# Microcontroller.net
KiCad netlist of a schematic drawn in Altium Designer
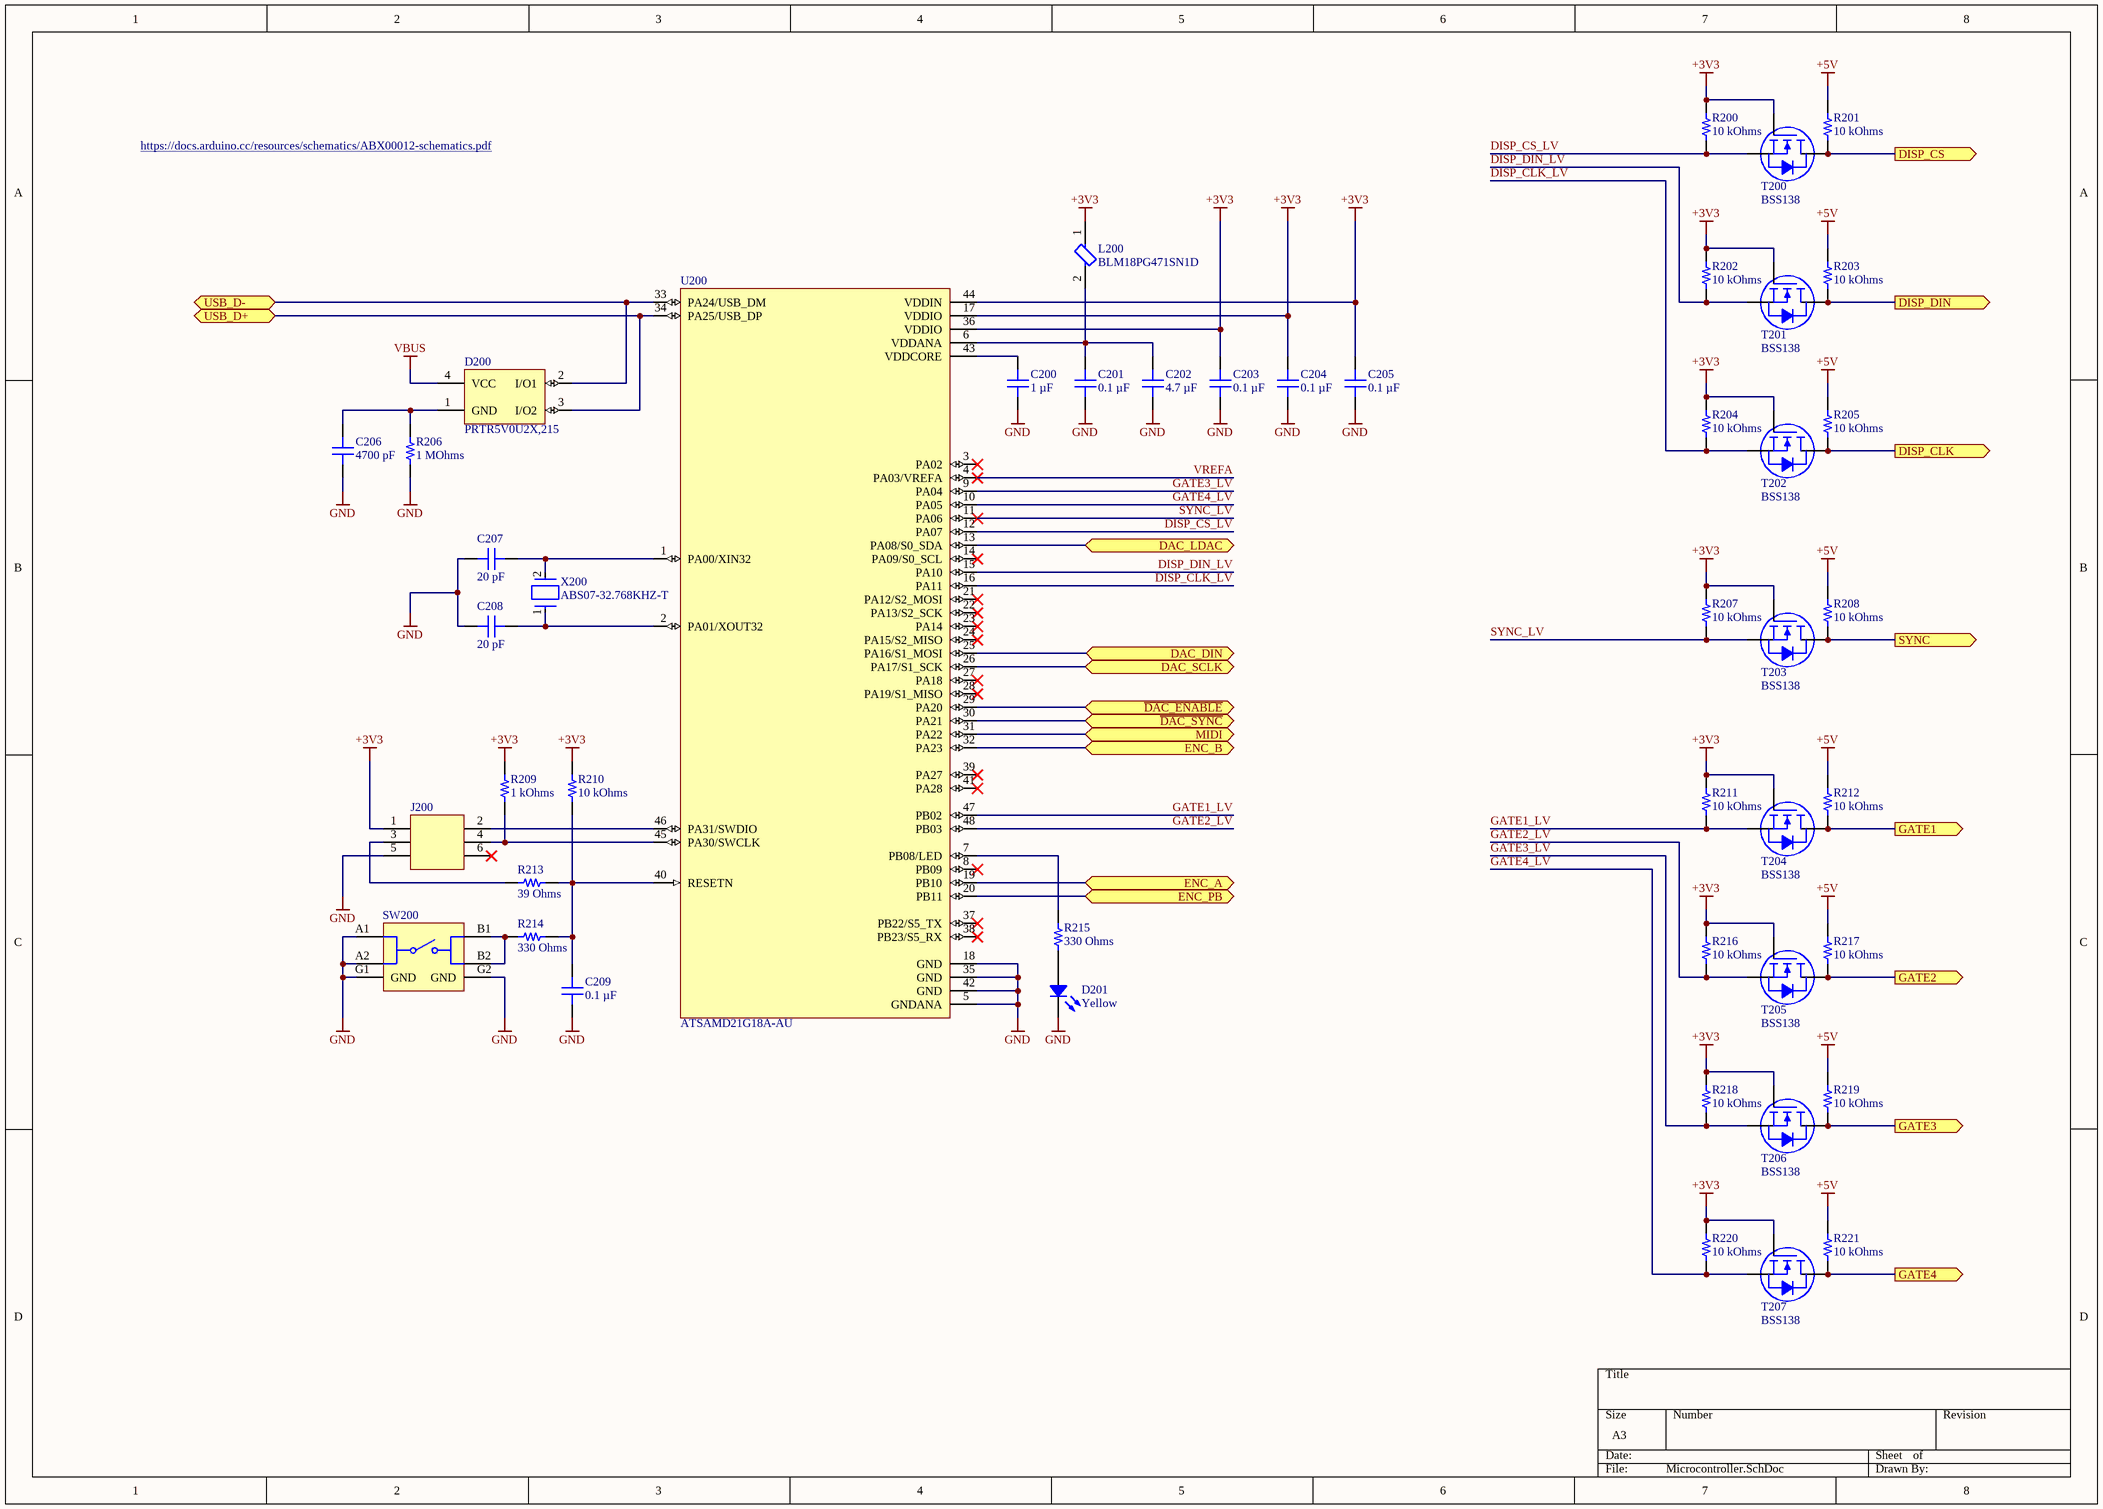
[diagram p0: Microcontroller.SchDoc]

(export (version "E")
  (design (tool "Eeschema 10.0.6"))
  (components
    (comp (ref "C200")
      (value "1 µF")
      (footprint "CAP 0603_1608")
      (description "CAP CER 1UF 10V X7R 0603")
      (fields (field (name "PART NUMBER") "CC0603KRX7R6BB105") (field (name "MANUFACTURER") "Yageo"))
      (libsource (lib "Celestial Altium Library") (part "Capacitor"))
    )
    (comp (ref "C201")
      (value "0.1 µF")
      (footprint "CAP 0603_1608")
      (description "CAP CER 0.1UF 16V X7R 0603")
      (fields (field (name "PART NUMBER") "CS0603KRX7R7BB104") (field (name "MANUFACTURER") "Yageo"))
      (libsource (lib "Celestial Altium Library") (part "Capacitor"))
    )
    (comp (ref "C202")
      (value "4.7 µF")
      (footprint "CAP 0603_1608")
      (description "CAP CER 4.7UF 10V X5R 0603")
      (fields (field (name "PART NUMBER") "CC0603MRX5R6BB475") (field (name "MANUFACTURER") "Yageo"))
      (libsource (lib "Celestial Altium Library") (part "Capacitor"))
    )
    (comp (ref "C203")
      (value "0.1 µF")
      (footprint "CAP 0603_1608")
      (description "CAP CER 0.1UF 16V X7R 0603")
      (fields (field (name "PART NUMBER") "CS0603KRX7R7BB104") (field (name "MANUFACTURER") "Yageo"))
      (libsource (lib "Celestial Altium Library") (part "Capacitor"))
    )
    (comp (ref "C204")
      (value "0.1 µF")
      (footprint "CAP 0603_1608")
      (description "CAP CER 0.1UF 16V X7R 0603")
      (fields (field (name "PART NUMBER") "CS0603KRX7R7BB104") (field (name "MANUFACTURER") "Yageo"))
      (libsource (lib "Celestial Altium Library") (part "Capacitor"))
    )
    (comp (ref "C205")
      (value "0.1 µF")
      (footprint "CAP 0603_1608")
      (description "CAP CER 0.1UF 16V X7R 0603")
      (fields (field (name "PART NUMBER") "CS0603KRX7R7BB104") (field (name "MANUFACTURER") "Yageo"))
      (libsource (lib "Celestial Altium Library") (part "Capacitor"))
    )
    (comp (ref "C206")
      (value "4700 pF")
      (footprint "CAP 0603_1608")
      (description "CAP CER 4700PF 50V X7R 0603")
      (fields (field (name "PART NUMBER") "CC0603JRX7R9BB472") (field (name "MANUFACTURER") "Yageo"))
      (libsource (lib "Celestial Altium Library") (part "Capacitor"))
    )
    (comp (ref "C207")
      (value "20 pF")
      (footprint "CAP 0603_1608")
      (description "CAP CER 20PF 50V C0G/NPO 0603")
      (fields (field (name "PART NUMBER") "CC0603JRNPO9BN200") (field (name "MANUFACTURER") "Yageo"))
      (libsource (lib "Celestial Altium Library") (part "Capacitor"))
    )
    (comp (ref "C208")
      (value "20 pF")
      (footprint "CAP 0603_1608")
      (description "CAP CER 20PF 50V C0G/NPO 0603")
      (fields (field (name "PART NUMBER") "CC0603JRNPO9BN200") (field (name "MANUFACTURER") "Yageo"))
      (libsource (lib "Celestial Altium Library") (part "Capacitor"))
    )
    (comp (ref "C209")
      (value "0.1 µF")
      (footprint "CAP 0603_1608")
      (description "CAP CER 0.1UF 16V X7R 0603")
      (fields (field (name "PART NUMBER") "CS0603KRX7R7BB104") (field (name "MANUFACTURER") "Yageo"))
      (libsource (lib "Celestial Altium Library") (part "Capacitor"))
    )
    (comp (ref "D200")
      (value "PRTR5V0U2X,215")
      (footprint "NXP-SOT143B-4_V")
      (fields (field (name "MANUFACTURER") "NXP Semiconductors"))
      (libsource (lib "LabratsSynthLib") (part "PRTR5V0U2X,215"))
    )
    (comp (ref "D201")
      (value "Yellow")
      (footprint "LED 0603_1608 YELLOW")
      (description "LED YELLOW 0603 SMD")
      (fields (field (name "PART NUMBER") "5990040007F") (field (name "MANUFACTURER") "Dialight"))
      (libsource (lib "Celestial Altium Library") (part "LED"))
    )
    (comp (ref "J200")
      (value "61030621121")
      (footprint "61030621121")
      (libsource (lib "LabratsSynthLib") (part "61030621121"))
    )
    (comp (ref "L200")
      (value "BLM18PG471SN1D")
      (footprint "FP-BLM18-0_15-t0_8-MFG")
      (description "Chip Ferrite Bead, 0603, 470Ω @ 100MHz, 0.2Ω, 25%, 1A")
      (fields (field (name "TOLERANCE") "25%"))
      (libsource (lib "Altium Content Vault") (part "5f30dd21d616792df468990f7003faa"))
    )
    (comp (ref "R200")
      (value "10 kOhms")
      (footprint "RES 0603_1608")
      (description "RES SMD 10K OHM 1% 1/10W 0603")
      (fields (field (name "PART NUMBER") "CRCW060310K0FKTA") (field (name "MANUFACTURER") "Vishay Dale"))
      (libsource (lib "Celestial Altium Library") (part "Resistor"))
    )
    (comp (ref "R201")
      (value "10 kOhms")
      (footprint "RES 0603_1608")
      (description "RES SMD 10K OHM 1% 1/10W 0603")
      (fields (field (name "PART NUMBER") "CRCW060310K0FKTA") (field (name "MANUFACTURER") "Vishay Dale"))
      (libsource (lib "Celestial Altium Library") (part "Resistor"))
    )
    (comp (ref "R202")
      (value "10 kOhms")
      (footprint "RES 0603_1608")
      (description "RES SMD 10K OHM 1% 1/10W 0603")
      (fields (field (name "PART NUMBER") "CRCW060310K0FKTA") (field (name "MANUFACTURER") "Vishay Dale"))
      (libsource (lib "Celestial Altium Library") (part "Resistor"))
    )
    (comp (ref "R203")
      (value "10 kOhms")
      (footprint "RES 0603_1608")
      (description "RES SMD 10K OHM 1% 1/10W 0603")
      (fields (field (name "PART NUMBER") "CRCW060310K0FKTA") (field (name "MANUFACTURER") "Vishay Dale"))
      (libsource (lib "Celestial Altium Library") (part "Resistor"))
    )
    (comp (ref "R204")
      (value "10 kOhms")
      (footprint "RES 0603_1608")
      (description "RES SMD 10K OHM 1% 1/10W 0603")
      (fields (field (name "PART NUMBER") "CRCW060310K0FKTA") (field (name "MANUFACTURER") "Vishay Dale"))
      (libsource (lib "Celestial Altium Library") (part "Resistor"))
    )
    (comp (ref "R205")
      (value "10 kOhms")
      (footprint "RES 0603_1608")
      (description "RES SMD 10K OHM 1% 1/10W 0603")
      (fields (field (name "PART NUMBER") "CRCW060310K0FKTA") (field (name "MANUFACTURER") "Vishay Dale"))
      (libsource (lib "Celestial Altium Library") (part "Resistor"))
    )
    (comp (ref "R206")
      (value "1 MOhms")
      (footprint "RES 0603_1608")
      (description "RES SMD 1M OHM 1% 1/10W 0603")
      (fields (field (name "PART NUMBER") "CRCW06031M00FKEA") (field (name "MANUFACTURER") "Vishay Dale"))
      (libsource (lib "Celestial Altium Library") (part "Resistor"))
    )
    (comp (ref "R207")
      (value "10 kOhms")
      (footprint "RES 0603_1608")
      (description "RES SMD 10K OHM 1% 1/10W 0603")
      (fields (field (name "PART NUMBER") "CRCW060310K0FKTA") (field (name "MANUFACTURER") "Vishay Dale"))
      (libsource (lib "Celestial Altium Library") (part "Resistor"))
    )
    (comp (ref "R208")
      (value "10 kOhms")
      (footprint "RES 0603_1608")
      (description "RES SMD 10K OHM 1% 1/10W 0603")
      (fields (field (name "PART NUMBER") "CRCW060310K0FKTA") (field (name "MANUFACTURER") "Vishay Dale"))
      (libsource (lib "Celestial Altium Library") (part "Resistor"))
    )
    (comp (ref "R209")
      (value "1 kOhms")
      (footprint "RES 0603_1608")
      (description "RES SMD 1K OHM 1% 1/10W 0603")
      (fields (field (name "PART NUMBER") "CRCW06031K00FKEB") (field (name "MANUFACTURER") "Vishay Dale"))
      (libsource (lib "Celestial Altium Library") (part "Resistor"))
    )
    (comp (ref "R210")
      (value "10 kOhms")
      (footprint "RES 0603_1608")
      (description "RES SMD 10K OHM 1% 1/10W 0603")
      (fields (field (name "PART NUMBER") "CRCW060310K0FKTA") (field (name "MANUFACTURER") "Vishay Dale"))
      (libsource (lib "Celestial Altium Library") (part "Resistor"))
    )
    (comp (ref "R211")
      (value "10 kOhms")
      (footprint "RES 0603_1608")
      (description "RES SMD 10K OHM 1% 1/10W 0603")
      (fields (field (name "PART NUMBER") "CRCW060310K0FKTA") (field (name "MANUFACTURER") "Vishay Dale"))
      (libsource (lib "Celestial Altium Library") (part "Resistor"))
    )
    (comp (ref "R212")
      (value "10 kOhms")
      (footprint "RES 0603_1608")
      (description "RES SMD 10K OHM 1% 1/10W 0603")
      (fields (field (name "PART NUMBER") "CRCW060310K0FKTA") (field (name "MANUFACTURER") "Vishay Dale"))
      (libsource (lib "Celestial Altium Library") (part "Resistor"))
    )
    (comp (ref "R213")
      (value "39 Ohms")
      (footprint "RES 0603_1608")
      (description "RES SMD 39 OHM 1% 1/10W 0603")
      (fields (field (name "PART NUMBER") "CRCW060339R0FKEA") (field (name "MANUFACTURER") "Vishay Dale"))
      (libsource (lib "Celestial Altium Library") (part "Resistor"))
    )
    (comp (ref "R214")
      (value "330 Ohms")
      (footprint "RES 0603_1608")
      (description "RES 330 OHM 1% 1/10W 0603")
      (fields (field (name "PART NUMBER") "CRCW0603330RFKEAC") (field (name "MANUFACTURER") "Vishay Dale"))
      (libsource (lib "Celestial Altium Library") (part "Resistor"))
    )
    (comp (ref "R215")
      (value "330 Ohms")
      (footprint "RES 0603_1608")
      (description "RES 330 OHM 1% 1/10W 0603")
      (fields (field (name "PART NUMBER") "CRCW0603330RFKEAC") (field (name "MANUFACTURER") "Vishay Dale"))
      (libsource (lib "Celestial Altium Library") (part "Resistor"))
    )
    (comp (ref "R216")
      (value "10 kOhms")
      (footprint "RES 0603_1608")
      (description "RES SMD 10K OHM 1% 1/10W 0603")
      (fields (field (name "PART NUMBER") "CRCW060310K0FKTA") (field (name "MANUFACTURER") "Vishay Dale"))
      (libsource (lib "Celestial Altium Library") (part "Resistor"))
    )
    (comp (ref "R217")
      (value "10 kOhms")
      (footprint "RES 0603_1608")
      (description "RES SMD 10K OHM 1% 1/10W 0603")
      (fields (field (name "PART NUMBER") "CRCW060310K0FKTA") (field (name "MANUFACTURER") "Vishay Dale"))
      (libsource (lib "Celestial Altium Library") (part "Resistor"))
    )
    (comp (ref "R218")
      (value "10 kOhms")
      (footprint "RES 0603_1608")
      (description "RES SMD 10K OHM 1% 1/10W 0603")
      (fields (field (name "PART NUMBER") "CRCW060310K0FKTA") (field (name "MANUFACTURER") "Vishay Dale"))
      (libsource (lib "Celestial Altium Library") (part "Resistor"))
    )
    (comp (ref "R219")
      (value "10 kOhms")
      (footprint "RES 0603_1608")
      (description "RES SMD 10K OHM 1% 1/10W 0603")
      (fields (field (name "PART NUMBER") "CRCW060310K0FKTA") (field (name "MANUFACTURER") "Vishay Dale"))
      (libsource (lib "Celestial Altium Library") (part "Resistor"))
    )
    (comp (ref "R220")
      (value "10 kOhms")
      (footprint "RES 0603_1608")
      (description "RES SMD 10K OHM 1% 1/10W 0603")
      (fields (field (name "PART NUMBER") "CRCW060310K0FKTA") (field (name "MANUFACTURER") "Vishay Dale"))
      (libsource (lib "Celestial Altium Library") (part "Resistor"))
    )
    (comp (ref "R221")
      (value "10 kOhms")
      (footprint "RES 0603_1608")
      (description "RES SMD 10K OHM 1% 1/10W 0603")
      (fields (field (name "PART NUMBER") "CRCW060310K0FKTA") (field (name "MANUFACTURER") "Vishay Dale"))
      (libsource (lib "Celestial Altium Library") (part "Resistor"))
    )
    (comp (ref "SW200")
      (value "435171014816")
      (footprint "435171014816")
      (description "Tactile Switch, Spst-no, 0.05A, 12V, SMD;")
      (libsource (lib "Altium Content Vault") (part "SPST-NO_4P_2GND"))
    )
    (comp (ref "T200")
      (value "BSS138")
      (footprint "ON SEMI SOT-23-3")
      (description "MOSFET N-CH 50V 220MA SOT-23")
      (fields (field (name "MANUFACTURER") "ON Semiconductor"))
      (libsource (lib "Celestial Altium Library") (part "ON SEMI MOSFET N-CH SOT-23-3"))
    )
    (comp (ref "T201")
      (value "BSS138")
      (footprint "ON SEMI SOT-23-3")
      (description "MOSFET N-CH 50V 220MA SOT-23")
      (fields (field (name "MANUFACTURER") "ON Semiconductor"))
      (libsource (lib "Celestial Altium Library") (part "ON SEMI MOSFET N-CH SOT-23-3"))
    )
    (comp (ref "T202")
      (value "BSS138")
      (footprint "ON SEMI SOT-23-3")
      (description "MOSFET N-CH 50V 220MA SOT-23")
      (fields (field (name "MANUFACTURER") "ON Semiconductor"))
      (libsource (lib "Celestial Altium Library") (part "ON SEMI MOSFET N-CH SOT-23-3"))
    )
    (comp (ref "T203")
      (value "BSS138")
      (footprint "ON SEMI SOT-23-3")
      (description "MOSFET N-CH 50V 220MA SOT-23")
      (fields (field (name "MANUFACTURER") "ON Semiconductor"))
      (libsource (lib "Celestial Altium Library") (part "ON SEMI MOSFET N-CH SOT-23-3"))
    )
    (comp (ref "T204")
      (value "BSS138")
      (footprint "ON SEMI SOT-23-3")
      (description "MOSFET N-CH 50V 220MA SOT-23")
      (fields (field (name "MANUFACTURER") "ON Semiconductor"))
      (libsource (lib "Celestial Altium Library") (part "ON SEMI MOSFET N-CH SOT-23-3"))
    )
    (comp (ref "T205")
      (value "BSS138")
      (footprint "ON SEMI SOT-23-3")
      (description "MOSFET N-CH 50V 220MA SOT-23")
      (fields (field (name "MANUFACTURER") "ON Semiconductor"))
      (libsource (lib "Celestial Altium Library") (part "ON SEMI MOSFET N-CH SOT-23-3"))
    )
    (comp (ref "T206")
      (value "BSS138")
      (footprint "ON SEMI SOT-23-3")
      (description "MOSFET N-CH 50V 220MA SOT-23")
      (fields (field (name "MANUFACTURER") "ON Semiconductor"))
      (libsource (lib "Celestial Altium Library") (part "ON SEMI MOSFET N-CH SOT-23-3"))
    )
    (comp (ref "T207")
      (value "BSS138")
      (footprint "ON SEMI SOT-23-3")
      (description "MOSFET N-CH 50V 220MA SOT-23")
      (fields (field (name "MANUFACTURER") "ON Semiconductor"))
      (libsource (lib "Celestial Altium Library") (part "ON SEMI MOSFET N-CH SOT-23-3"))
    )
    (comp (ref "U200")
      (value "ATSAMD21G18A-AU")
      (footprint "ATML-TQFP48")
      (fields (field (name "MANUFACTURER") "Atmel"))
      (libsource (lib "LabratsSynthLib") (part "ATSAMD21G18A-AU"))
    )
    (comp (ref "X200")
      (value "ABS07-32.768KHZ-T")
      (footprint "FP-ABS07-MFG")
      (description "Crystal 32.768kHz ±20ppm (Tol) 12.5pF FUND 70kΩ 2-Pin CSMD T/R")
      (fields (field (name "TOLERANCE") "20ppm"))
      (libsource (lib "Altium Content Vault") (part "c23a69dc6c9e2f18f2079038eb95dd1"))
    )
  )
  (nets
    (net (code "1") (name "+3V3") (class "Default")
      (node (ref "C203") (pin "2") (pinfunction "2_2") (pintype "passive"))
      (node (ref "C204") (pin "2") (pinfunction "2_2") (pintype "passive"))
      (node (ref "C205") (pin "2") (pinfunction "2_2") (pintype "passive"))
      (node (ref "J200") (pin "1") (pinfunction "1_1") (pintype "passive"))
      (node (ref "L200") (pin "1") (pinfunction "1_1") (pintype "passive"))
      (node (ref "R200") (pin "2") (pinfunction "2_2") (pintype "passive"))
      (node (ref "R202") (pin "2") (pinfunction "2_2") (pintype "passive"))
      (node (ref "R204") (pin "2") (pinfunction "2_2") (pintype "passive"))
      (node (ref "R207") (pin "2") (pinfunction "2_2") (pintype "passive"))
      (node (ref "R209") (pin "2") (pinfunction "2_2") (pintype "passive"))
      (node (ref "R210") (pin "2") (pinfunction "2_2") (pintype "passive"))
      (node (ref "R211") (pin "2") (pinfunction "2_2") (pintype "passive"))
      (node (ref "R216") (pin "2") (pinfunction "2_2") (pintype "passive"))
      (node (ref "R218") (pin "2") (pinfunction "2_2") (pintype "passive"))
      (node (ref "R220") (pin "2") (pinfunction "2_2") (pintype "passive"))
      (node (ref "T200") (pin "1") (pinfunction "G_1") (pintype "passive"))
      (node (ref "T201") (pin "1") (pinfunction "G_1") (pintype "passive"))
      (node (ref "T202") (pin "1") (pinfunction "G_1") (pintype "passive"))
      (node (ref "T203") (pin "1") (pinfunction "G_1") (pintype "passive"))
      (node (ref "T204") (pin "1") (pinfunction "G_1") (pintype "passive"))
      (node (ref "T205") (pin "1") (pinfunction "G_1") (pintype "passive"))
      (node (ref "T206") (pin "1") (pinfunction "G_1") (pintype "passive"))
      (node (ref "T207") (pin "1") (pinfunction "G_1") (pintype "passive"))
      (node (ref "U200") (pin "17") (pinfunction "VDDIO_17") (pintype "power_in"))
      (node (ref "U200") (pin "36") (pinfunction "VDDIO_36") (pintype "power_in"))
      (node (ref "U200") (pin "44") (pinfunction "VDDIN_44") (pintype "power_in"))
    )
    (net (code "2") (name "+5V") (class "Default")
      (node (ref "R201") (pin "2") (pinfunction "2_2") (pintype "passive"))
      (node (ref "R203") (pin "2") (pinfunction "2_2") (pintype "passive"))
      (node (ref "R205") (pin "2") (pinfunction "2_2") (pintype "passive"))
      (node (ref "R208") (pin "2") (pinfunction "2_2") (pintype "passive"))
      (node (ref "R212") (pin "2") (pinfunction "2_2") (pintype "passive"))
      (node (ref "R217") (pin "2") (pinfunction "2_2") (pintype "passive"))
      (node (ref "R219") (pin "2") (pinfunction "2_2") (pintype "passive"))
      (node (ref "R221") (pin "2") (pinfunction "2_2") (pintype "passive"))
    )
    (net (code "3") (name "/DAC_DIN") (class "Default")
      (node (ref "U200") (pin "25") (pinfunction "PA16/S1_MOSI_25") (pintype "bidirectional"))
    )
    (net (code "4") (name "/DAC_LDAC") (class "Default")
      (node (ref "U200") (pin "13") (pinfunction "PA08/S0_SDA_13") (pintype "bidirectional"))
    )
    (net (code "5") (name "/DAC_SCLK") (class "Default")
      (node (ref "U200") (pin "26") (pinfunction "PA17/S1_SCK_26") (pintype "bidirectional"))
    )
    (net (code "6") (name "/DISP_CLK") (class "Default")
      (node (ref "R205") (pin "1") (pinfunction "1_1") (pintype "passive"))
      (node (ref "T202") (pin "3") (pinfunction "D_3") (pintype "passive"))
    )
    (net (code "7") (name "/DISP_CLK_LV") (class "Default")
      (node (ref "R204") (pin "1") (pinfunction "1_1") (pintype "passive"))
      (node (ref "T202") (pin "2") (pinfunction "S_2") (pintype "passive"))
      (node (ref "U200") (pin "16") (pinfunction "PA11_16") (pintype "bidirectional"))
    )
    (net (code "8") (name "/DISP_CS") (class "Default")
      (node (ref "R201") (pin "1") (pinfunction "1_1") (pintype "passive"))
      (node (ref "T200") (pin "3") (pinfunction "D_3") (pintype "passive"))
    )
    (net (code "9") (name "/DISP_CS_LV") (class "Default")
      (node (ref "R200") (pin "1") (pinfunction "1_1") (pintype "passive"))
      (node (ref "T200") (pin "2") (pinfunction "S_2") (pintype "passive"))
      (node (ref "U200") (pin "12") (pinfunction "PA07_12") (pintype "bidirectional"))
    )
    (net (code "10") (name "/DISP_DIN") (class "Default")
      (node (ref "R203") (pin "1") (pinfunction "1_1") (pintype "passive"))
      (node (ref "T201") (pin "3") (pinfunction "D_3") (pintype "passive"))
    )
    (net (code "11") (name "/DISP_DIN_LV") (class "Default")
      (node (ref "R202") (pin "1") (pinfunction "1_1") (pintype "passive"))
      (node (ref "T201") (pin "2") (pinfunction "S_2") (pintype "passive"))
      (node (ref "U200") (pin "15") (pinfunction "PA10_15") (pintype "bidirectional"))
    )
    (net (code "12") (name "/ENC_A") (class "Default")
      (node (ref "U200") (pin "19") (pinfunction "PB10_19") (pintype "bidirectional"))
    )
    (net (code "13") (name "/ENC_B") (class "Default")
      (node (ref "U200") (pin "32") (pinfunction "PA23_32") (pintype "bidirectional"))
    )
    (net (code "14") (name "/ENC_PB") (class "Default")
      (node (ref "U200") (pin "20") (pinfunction "PB11_20") (pintype "bidirectional"))
    )
    (net (code "15") (name "/GATE1") (class "Default")
      (node (ref "R212") (pin "1") (pinfunction "1_1") (pintype "passive"))
      (node (ref "T204") (pin "3") (pinfunction "D_3") (pintype "passive"))
    )
    (net (code "16") (name "/GATE1_LV") (class "Default")
      (node (ref "R211") (pin "1") (pinfunction "1_1") (pintype "passive"))
      (node (ref "T204") (pin "2") (pinfunction "S_2") (pintype "passive"))
      (node (ref "U200") (pin "47") (pinfunction "PB02_47") (pintype "bidirectional"))
    )
    (net (code "17") (name "/GATE2") (class "Default")
      (node (ref "R217") (pin "1") (pinfunction "1_1") (pintype "passive"))
      (node (ref "T205") (pin "3") (pinfunction "D_3") (pintype "passive"))
    )
    (net (code "18") (name "/GATE2_LV") (class "Default")
      (node (ref "R216") (pin "1") (pinfunction "1_1") (pintype "passive"))
      (node (ref "T205") (pin "2") (pinfunction "S_2") (pintype "passive"))
      (node (ref "U200") (pin "48") (pinfunction "PB03_48") (pintype "bidirectional"))
    )
    (net (code "19") (name "/GATE3") (class "Default")
      (node (ref "R219") (pin "1") (pinfunction "1_1") (pintype "passive"))
      (node (ref "T206") (pin "3") (pinfunction "D_3") (pintype "passive"))
    )
    (net (code "20") (name "/GATE3_LV") (class "Default")
      (node (ref "R218") (pin "1") (pinfunction "1_1") (pintype "passive"))
      (node (ref "T206") (pin "2") (pinfunction "S_2") (pintype "passive"))
      (node (ref "U200") (pin "9") (pinfunction "PA04_9") (pintype "bidirectional"))
    )
    (net (code "21") (name "/GATE4") (class "Default")
      (node (ref "R221") (pin "1") (pinfunction "1_1") (pintype "passive"))
      (node (ref "T207") (pin "3") (pinfunction "D_3") (pintype "passive"))
    )
    (net (code "22") (name "/GATE4_LV") (class "Default")
      (node (ref "R220") (pin "1") (pinfunction "1_1") (pintype "passive"))
      (node (ref "T207") (pin "2") (pinfunction "S_2") (pintype "passive"))
      (node (ref "U200") (pin "10") (pinfunction "PA05_10") (pintype "bidirectional"))
    )
    (net (code "23") (name "/MIDI") (class "Default")
      (node (ref "U200") (pin "31") (pinfunction "PA22_31") (pintype "bidirectional"))
    )
    (net (code "24") (name "/SYNC") (class "Default")
      (node (ref "R208") (pin "1") (pinfunction "1_1") (pintype "passive"))
      (node (ref "T203") (pin "3") (pinfunction "D_3") (pintype "passive"))
    )
    (net (code "25") (name "/SYNC_LV") (class "Default")
      (node (ref "R207") (pin "1") (pinfunction "1_1") (pintype "passive"))
      (node (ref "T203") (pin "2") (pinfunction "S_2") (pintype "passive"))
      (node (ref "U200") (pin "11") (pinfunction "PA06_11") (pintype "bidirectional"))
    )
    (net (code "26") (name "/USB_D+") (class "Default")
      (node (ref "D200") (pin "3") (pinfunction "I/O2_3") (pintype "bidirectional"))
      (node (ref "U200") (pin "34") (pinfunction "PA25/USB_DP_34") (pintype "bidirectional"))
    )
    (net (code "27") (name "/USB_D-") (class "Default")
      (node (ref "D200") (pin "2") (pinfunction "I/O1_2") (pintype "bidirectional"))
      (node (ref "U200") (pin "33") (pinfunction "PA24/USB_DM_33") (pintype "bidirectional"))
    )
    (net (code "28") (name "/VREFA") (class "Default")
      (node (ref "U200") (pin "4") (pinfunction "PA03/VREFA_4") (pintype "bidirectional+no_connect"))
    )
    (net (code "29") (name "/~{DAC_ENABLE}") (class "Default")
      (node (ref "U200") (pin "29") (pinfunction "PA20_29") (pintype "bidirectional"))
    )
    (net (code "30") (name "/~{DAC_SYNC}") (class "Default")
      (node (ref "U200") (pin "30") (pinfunction "PA21_30") (pintype "bidirectional"))
    )
    (net (code "31") (name "GND") (class "Default")
      (node (ref "C200") (pin "1") (pinfunction "1_1") (pintype "passive"))
      (node (ref "C201") (pin "1") (pinfunction "1_1") (pintype "passive"))
      (node (ref "C202") (pin "1") (pinfunction "1_1") (pintype "passive"))
      (node (ref "C203") (pin "1") (pinfunction "1_1") (pintype "passive"))
      (node (ref "C204") (pin "1") (pinfunction "1_1") (pintype "passive"))
      (node (ref "C205") (pin "1") (pinfunction "1_1") (pintype "passive"))
      (node (ref "C206") (pin "1") (pinfunction "1_1") (pintype "passive"))
      (node (ref "C207") (pin "1") (pinfunction "1_1") (pintype "passive"))
      (node (ref "C208") (pin "1") (pinfunction "1_1") (pintype "passive"))
      (node (ref "C209") (pin "1") (pinfunction "1_1") (pintype "passive"))
      (node (ref "D201") (pin "2") (pinfunction "2_2") (pintype "passive"))
      (node (ref "J200") (pin "5") (pinfunction "5_5") (pintype "passive"))
      (node (ref "R206") (pin "1") (pinfunction "1_1") (pintype "passive"))
      (node (ref "SW200") (pin "A1") (pinfunction "A1_A1") (pintype "passive"))
      (node (ref "SW200") (pin "A2") (pinfunction "A2_A2") (pintype "passive"))
      (node (ref "SW200") (pin "G1") (pinfunction "GND_G1") (pintype "passive"))
      (node (ref "SW200") (pin "G2") (pinfunction "GND_G2") (pintype "passive"))
      (node (ref "U200") (pin "18") (pinfunction "GND_18") (pintype "power_in"))
      (node (ref "U200") (pin "35") (pinfunction "GND_35") (pintype "power_in"))
      (node (ref "U200") (pin "42") (pinfunction "GND_42") (pintype "power_in"))
      (node (ref "U200") (pin "5") (pinfunction "GNDANA_5") (pintype "power_in"))
    )
    (net (code "32") (name "Net-(D200-GND)") (class "Default")
      (node (ref "C206") (pin "2") (pinfunction "2_2") (pintype "passive"))
      (node (ref "D200") (pin "1") (pinfunction "GND_1") (pintype "power_in"))
      (node (ref "R206") (pin "2") (pinfunction "2_2") (pintype "passive"))
    )
    (net (code "33") (name "Net-(D201-Pad1)") (class "Default")
      (node (ref "D201") (pin "1") (pinfunction "1_1") (pintype "passive"))
      (node (ref "R215") (pin "2") (pinfunction "2_2") (pintype "passive"))
    )
    (net (code "34") (name "Net-(J200-Pad3)") (class "Default")
      (node (ref "J200") (pin "3") (pinfunction "3_3") (pintype "passive"))
      (node (ref "R213") (pin "1") (pinfunction "1_1") (pintype "passive"))
    )
    (net (code "35") (name "Net-(R214-Pad1)") (class "Default")
      (node (ref "R214") (pin "1") (pinfunction "1_1") (pintype "passive"))
      (node (ref "SW200") (pin "B1") (pinfunction "B1_B1") (pintype "passive"))
      (node (ref "SW200") (pin "B2") (pinfunction "B2_B2") (pintype "passive"))
    )
    (net (code "36") (name "Net-(U200-PA00{slash}XIN32)") (class "Default")
      (node (ref "C207") (pin "2") (pinfunction "2_2") (pintype "passive"))
      (node (ref "U200") (pin "1") (pinfunction "PA00/XIN32_1") (pintype "bidirectional"))
      (node (ref "X200") (pin "2") (pinfunction "2_2") (pintype "passive"))
    )
    (net (code "37") (name "Net-(U200-PA01{slash}XOUT32)") (class "Default")
      (node (ref "C208") (pin "2") (pinfunction "2_2") (pintype "passive"))
      (node (ref "U200") (pin "2") (pinfunction "PA01/XOUT32_2") (pintype "bidirectional"))
      (node (ref "X200") (pin "1") (pinfunction "1_1") (pintype "passive"))
    )
    (net (code "38") (name "Net-(U200-PA30{slash}SWCLK)") (class "Default")
      (node (ref "J200") (pin "4") (pinfunction "4_4") (pintype "passive"))
      (node (ref "R209") (pin "1") (pinfunction "1_1") (pintype "passive"))
      (node (ref "U200") (pin "45") (pinfunction "PA30/SWCLK_45") (pintype "bidirectional"))
    )
    (net (code "39") (name "Net-(U200-PA31{slash}SWDIO)") (class "Default")
      (node (ref "J200") (pin "2") (pinfunction "2_2") (pintype "passive"))
      (node (ref "U200") (pin "46") (pinfunction "PA31/SWDIO_46") (pintype "bidirectional"))
    )
    (net (code "40") (name "Net-(U200-PB08{slash}LED)") (class "Default")
      (node (ref "R215") (pin "1") (pinfunction "1_1") (pintype "passive"))
      (node (ref "U200") (pin "7") (pinfunction "PB08/LED_7") (pintype "bidirectional"))
    )
    (net (code "41") (name "Net-(U200-RESETN)") (class "Default")
      (node (ref "C209") (pin "2") (pinfunction "2_2") (pintype "passive"))
      (node (ref "R210") (pin "1") (pinfunction "1_1") (pintype "passive"))
      (node (ref "R213") (pin "2") (pinfunction "2_2") (pintype "passive"))
      (node (ref "R214") (pin "2") (pinfunction "2_2") (pintype "passive"))
      (node (ref "U200") (pin "40") (pinfunction "RESETN_40") (pintype "input"))
    )
    (net (code "42") (name "Net-(U200-VDDANA)") (class "Default")
      (node (ref "C201") (pin "2") (pinfunction "2_2") (pintype "passive"))
      (node (ref "C202") (pin "2") (pinfunction "2_2") (pintype "passive"))
      (node (ref "L200") (pin "2") (pinfunction "2_2") (pintype "passive"))
      (node (ref "U200") (pin "6") (pinfunction "VDDANA_6") (pintype "power_in"))
    )
    (net (code "43") (name "Net-(U200-VDDCORE)") (class "Default")
      (node (ref "C200") (pin "2") (pinfunction "2_2") (pintype "passive"))
      (node (ref "U200") (pin "43") (pinfunction "VDDCORE_43") (pintype "power_in"))
    )
    (net (code "44") (name "VBUS") (class "Default")
      (node (ref "D200") (pin "4") (pinfunction "VCC_4") (pintype "power_in"))
    )
    (net (code "45") (name "unconnected-(J200-Pad6)") (class "Default")
      (node (ref "J200") (pin "6") (pinfunction "6_6") (pintype "passive+no_connect"))
    )
    (net (code "46") (name "unconnected-(U200-PA02-Pad3)") (class "Default")
      (node (ref "U200") (pin "3") (pinfunction "PA02_3") (pintype "bidirectional+no_connect"))
    )
    (net (code "47") (name "unconnected-(U200-PA09{slash}S0_SCL-Pad14)") (class "Default")
      (node (ref "U200") (pin "14") (pinfunction "PA09/S0_SCL_14") (pintype "bidirectional+no_connect"))
    )
    (net (code "48") (name "unconnected-(U200-PA12{slash}S2_MOSI-Pad21)") (class "Default")
      (node (ref "U200") (pin "21") (pinfunction "PA12/S2_MOSI_21") (pintype "bidirectional+no_connect"))
    )
    (net (code "49") (name "unconnected-(U200-PA13{slash}S2_SCK-Pad22)") (class "Default")
      (node (ref "U200") (pin "22") (pinfunction "PA13/S2_SCK_22") (pintype "bidirectional+no_connect"))
    )
    (net (code "50") (name "unconnected-(U200-PA14-Pad23)") (class "Default")
      (node (ref "U200") (pin "23") (pinfunction "PA14_23") (pintype "bidirectional+no_connect"))
    )
    (net (code "51") (name "unconnected-(U200-PA15{slash}S2_MISO-Pad24)") (class "Default")
      (node (ref "U200") (pin "24") (pinfunction "PA15/S2_MISO_24") (pintype "bidirectional+no_connect"))
    )
    (net (code "52") (name "unconnected-(U200-PA18-Pad27)") (class "Default")
      (node (ref "U200") (pin "27") (pinfunction "PA18_27") (pintype "bidirectional+no_connect"))
    )
    (net (code "53") (name "unconnected-(U200-PA19{slash}S1_MISO-Pad28)") (class "Default")
      (node (ref "U200") (pin "28") (pinfunction "PA19/S1_MISO_28") (pintype "bidirectional+no_connect"))
    )
    (net (code "54") (name "unconnected-(U200-PA27-Pad39)") (class "Default")
      (node (ref "U200") (pin "39") (pinfunction "PA27_39") (pintype "bidirectional+no_connect"))
    )
    (net (code "55") (name "unconnected-(U200-PA28-Pad41)") (class "Default")
      (node (ref "U200") (pin "41") (pinfunction "PA28_41") (pintype "bidirectional+no_connect"))
    )
    (net (code "56") (name "unconnected-(U200-PB09-Pad8)") (class "Default")
      (node (ref "U200") (pin "8") (pinfunction "PB09_8") (pintype "bidirectional+no_connect"))
    )
    (net (code "57") (name "unconnected-(U200-PB22{slash}S5_TX-Pad37)") (class "Default")
      (node (ref "U200") (pin "37") (pinfunction "PB22/S5_TX_37") (pintype "bidirectional+no_connect"))
    )
    (net (code "58") (name "unconnected-(U200-PB23{slash}S5_RX-Pad38)") (class "Default")
      (node (ref "U200") (pin "38") (pinfunction "PB23/S5_RX_38") (pintype "bidirectional+no_connect"))
    )
  )
)
